# G3108.net
KiCad netlist of a schematic drawn in EasyEDA Pro
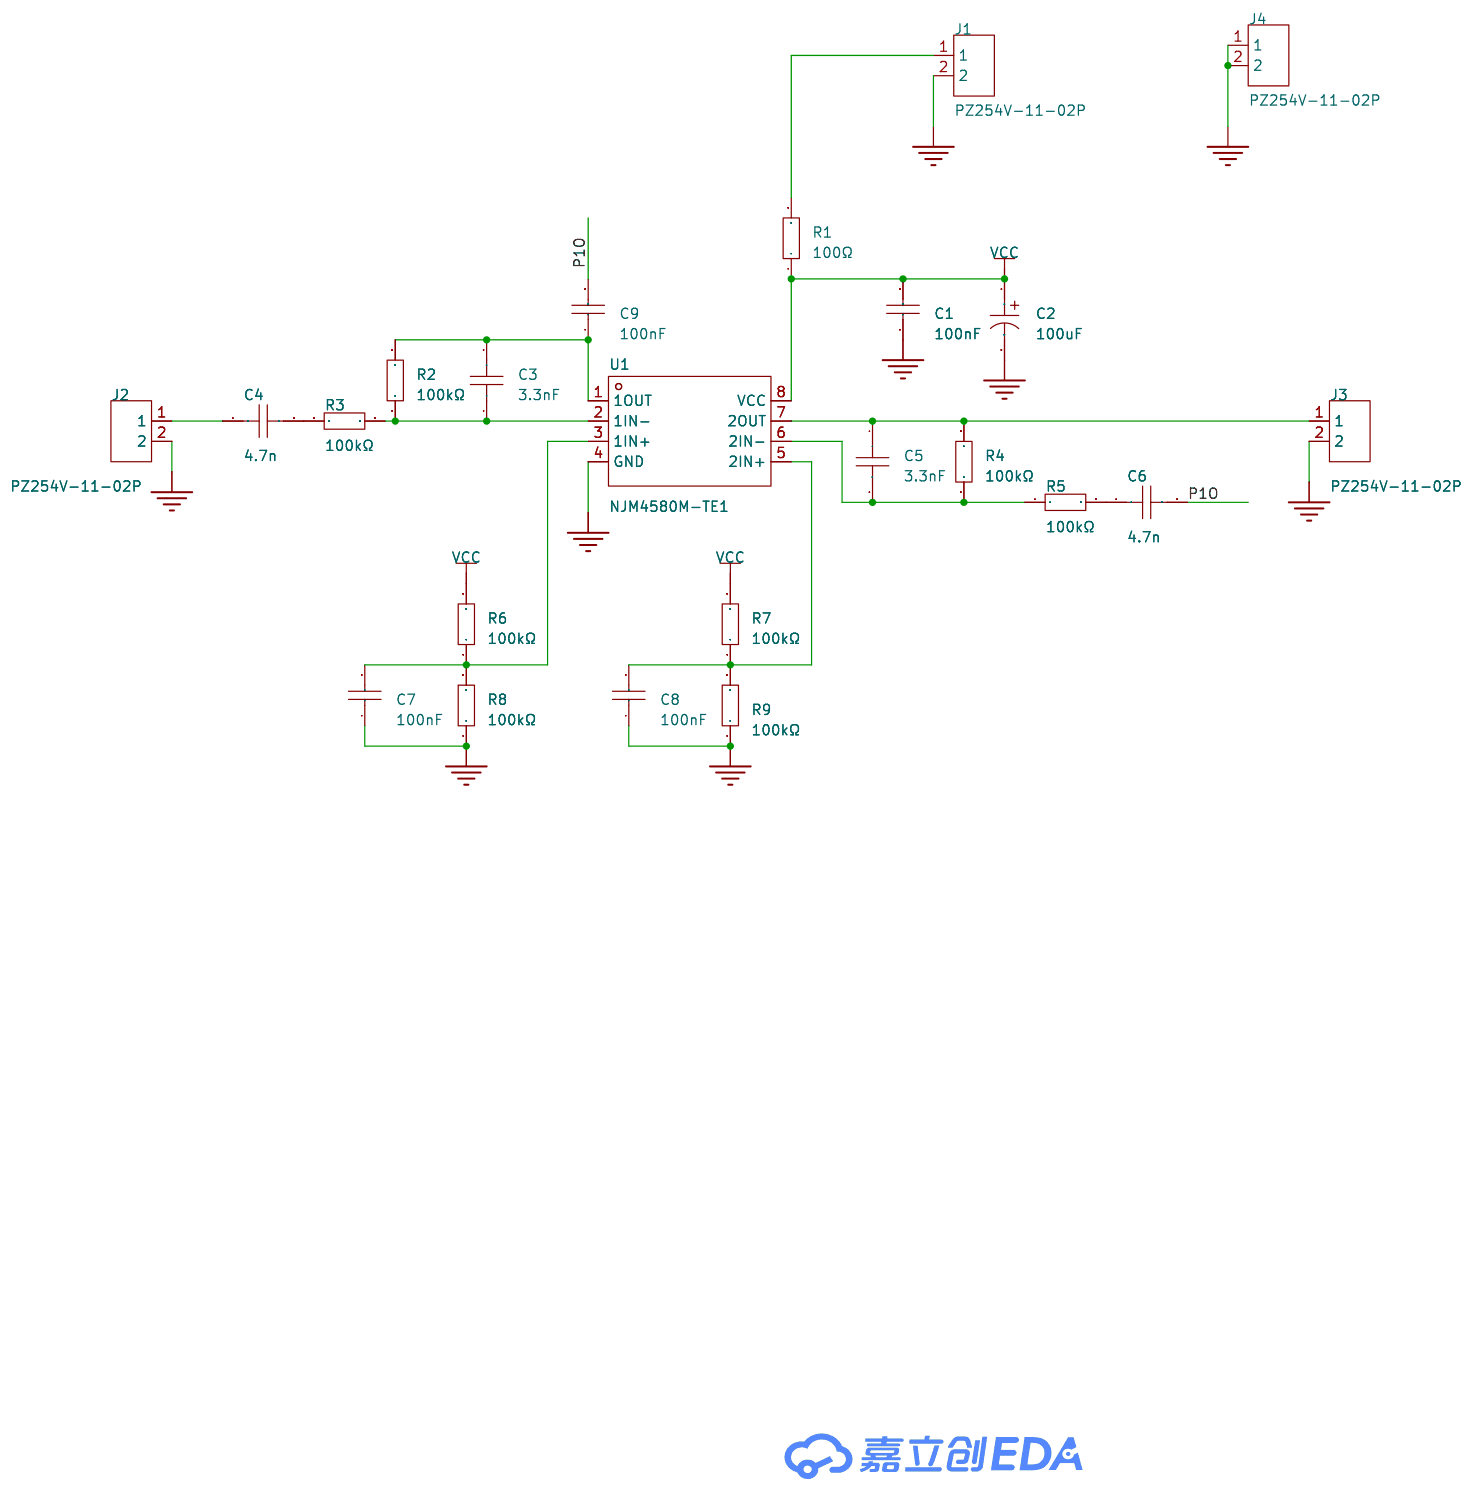
[diagram p0: schematic sheet]

(export (version "E")
  (design (tool "Eeschema 10.0.6"))
  (components
    (comp (ref "C1")
      (value "100nF")
      (footprint "easyedapro:C0603")
      (description "容值:100nF;精度:±5%;额定电压:50V;材质(温度系数):X7R;")
      (fields
        (field (name "Manufacturer Part") "CC0603JRX7R9BB104")
        (field (name "Manufacturer") "YAGEO(国巨)")
      )
      (libsource (lib "easyedapro") (part "CC0603JRX7R9BB104"))
    )
    (comp (ref "C2")
      (value "100uF")
      (footprint "easyedapro:CAP-SMD_L3.2-W1.6")
      (description "容值:100uF;精度:±20%;额定电压:7V;等效串联电阻(ESR):70mΩ@100kHz;")
      (fields
        (field (name "Manufacturer Part") "T55A107M007C0070")
        (field (name "Manufacturer") "VISHAY(威世)")
      )
      (libsource (lib "easyedapro") (part "T55A107M007C0070"))
    )
    (comp (ref "C3")
      (value "3.3nF")
      (footprint "easyedapro:C0603")
      (description "容值:3.3nF;精度:±1%;额定电压:50V;温度系数:NP0;")
      (fields
        (field (name "Manufacturer Part") "CC0603FRNPO9BN332")
        (field (name "Manufacturer") "YAGEO(国巨)")
      )
      (libsource (lib "easyedapro") (part "CC0603FRNPO9BN332"))
    )
    (comp (ref "C4")
      (value "4.7n")
      (footprint "easyedapro:C0603")
      (description "容值:3.3nF;精度:±1%;额定电压:50V;温度系数:NP0;")
      (fields
        (field (name "Manufacturer Part") "CC0603FRNPO9BN332")
        (field (name "Manufacturer") "YAGEO(国巨)")
      )
      (libsource (lib "easyedapro") (part "CC0603FRNPO9BN332"))
    )
    (comp (ref "C5")
      (value "3.3nF")
      (footprint "easyedapro:C0603")
      (description "容值:3.3nF;精度:±1%;额定电压:50V;温度系数:NP0;")
      (fields
        (field (name "Manufacturer Part") "CC0603FRNPO9BN332")
        (field (name "Manufacturer") "YAGEO(国巨)")
      )
      (libsource (lib "easyedapro") (part "CC0603FRNPO9BN332"))
    )
    (comp (ref "C6")
      (value "4.7n")
      (footprint "easyedapro:C0603")
      (description "容值:3.3nF;精度:±1%;额定电压:50V;温度系数:NP0;")
      (fields
        (field (name "Manufacturer Part") "CC0603FRNPO9BN332")
        (field (name "Manufacturer") "YAGEO(国巨)")
      )
      (libsource (lib "easyedapro") (part "CC0603FRNPO9BN332"))
    )
    (comp (ref "C7")
      (value "100nF")
      (footprint "easyedapro:C0603")
      (description "容值:100nF;精度:±5%;额定电压:50V;材质(温度系数):X7R;")
      (fields
        (field (name "Manufacturer Part") "CC0603JRX7R9BB104")
        (field (name "Manufacturer") "YAGEO(国巨)")
      )
      (libsource (lib "easyedapro") (part "CC0603JRX7R9BB104"))
    )
    (comp (ref "C8")
      (value "100nF")
      (footprint "easyedapro:C0603")
      (description "容值:100nF;精度:±5%;额定电压:50V;材质(温度系数):X7R;")
      (fields
        (field (name "Manufacturer Part") "CC0603JRX7R9BB104")
        (field (name "Manufacturer") "YAGEO(国巨)")
      )
      (libsource (lib "easyedapro") (part "CC0603JRX7R9BB104"))
    )
    (comp (ref "C9")
      (value "100nF")
      (footprint "easyedapro:C0603")
      (description "容值:100nF;精度:±5%;额定电压:50V;材质(温度系数):X7R;")
      (fields
        (field (name "Manufacturer Part") "CC0603JRX7R9BB104")
        (field (name "Manufacturer") "YAGEO(国巨)")
      )
      (libsource (lib "easyedapro") (part "CC0603JRX7R9BB104"))
    )
    (comp (ref "J1")
      (value "PZ254V-11-02P")
      (footprint "easyedapro:HDR-TH_2P-P2.54-V-M")
      (fields (field (name "Manufacturer") "XFCN(兴飞)"))
      (libsource (lib "easyedapro") (part "PZ254V-11-02P"))
    )
    (comp (ref "J2")
      (value "PZ254V-11-02P")
      (footprint "easyedapro:HDR-TH_2P-P2.54-V-M")
      (fields (field (name "Manufacturer") "XFCN(兴飞)"))
      (libsource (lib "easyedapro") (part "PZ254V-11-02P"))
    )
    (comp (ref "J3")
      (value "PZ254V-11-02P")
      (footprint "easyedapro:HDR-TH_2P-P2.54-V-M")
      (fields (field (name "Manufacturer") "XFCN(兴飞)"))
      (libsource (lib "easyedapro") (part "PZ254V-11-02P"))
    )
    (comp (ref "J4")
      (value "PZ254V-11-02P")
      (footprint "easyedapro:HDR-TH_2P-P2.54-V-M")
      (fields (field (name "Manufacturer") "XFCN(兴飞)"))
      (libsource (lib "easyedapro") (part "PZ254V-11-02P"))
    )
    (comp (ref "R1")
      (value "100Ω")
      (footprint "easyedapro:R0603")
      (description "电阻类型:厚膜电阻;阻值:100Ω;精度:±1%;功率:100mW;最大工作电压:75V;温度系数:±100ppm/°C;")
      (fields (field (name "Manufacturer Part") "RC0603FR-07100RL") (field (name "Manufacturer") "YAGEO(国巨)"))
      (libsource (lib "easyedapro") (part "RC0603FR-07100RL"))
    )
    (comp (ref "R2")
      (value "100kΩ")
      (footprint "easyedapro:R0603")
      (description "电阻类型:厚膜电阻;阻值:100kΩ;精度:±1%;功率:100mW;最大工作电压:75V;温度系数:±100ppm/°C;")
      (fields (field (name "Manufacturer Part") "RC0603FR-07100KL") (field (name "Manufacturer") "YAGEO(国巨)"))
      (libsource (lib "easyedapro") (part "RC0603FR-07100KL"))
    )
    (comp (ref "R3")
      (value "100kΩ")
      (footprint "easyedapro:R0603")
      (description "电阻类型:厚膜电阻;阻值:100kΩ;精度:±1%;功率:100mW;最大工作电压:75V;温度系数:±100ppm/°C;")
      (fields (field (name "Manufacturer Part") "RC0603FR-07100KL") (field (name "Manufacturer") "YAGEO(国巨)"))
      (libsource (lib "easyedapro") (part "RC0603FR-07100KL"))
    )
    (comp (ref "R4")
      (value "100kΩ")
      (footprint "easyedapro:R0603")
      (description "电阻类型:厚膜电阻;阻值:100kΩ;精度:±1%;功率:100mW;最大工作电压:75V;温度系数:±100ppm/°C;")
      (fields (field (name "Manufacturer Part") "RC0603FR-07100KL") (field (name "Manufacturer") "YAGEO(国巨)"))
      (libsource (lib "easyedapro") (part "RC0603FR-07100KL"))
    )
    (comp (ref "R5")
      (value "100kΩ")
      (footprint "easyedapro:R0603")
      (description "电阻类型:厚膜电阻;阻值:100kΩ;精度:±1%;功率:100mW;最大工作电压:75V;温度系数:±100ppm/°C;")
      (fields (field (name "Manufacturer Part") "RC0603FR-07100KL") (field (name "Manufacturer") "YAGEO(国巨)"))
      (libsource (lib "easyedapro") (part "RC0603FR-07100KL"))
    )
    (comp (ref "R6")
      (value "100kΩ")
      (footprint "easyedapro:R0603")
      (description "电阻类型:厚膜电阻;阻值:100kΩ;精度:±1%;功率:100mW;最大工作电压:75V;温度系数:±100ppm/°C;")
      (fields (field (name "Manufacturer Part") "RC0603FR-07100KL") (field (name "Manufacturer") "YAGEO(国巨)"))
      (libsource (lib "easyedapro") (part "RC0603FR-07100KL"))
    )
    (comp (ref "R7")
      (value "100kΩ")
      (footprint "easyedapro:R0603")
      (description "电阻类型:厚膜电阻;阻值:100kΩ;精度:±1%;功率:100mW;最大工作电压:75V;温度系数:±100ppm/°C;")
      (fields (field (name "Manufacturer Part") "RC0603FR-07100KL") (field (name "Manufacturer") "YAGEO(国巨)"))
      (libsource (lib "easyedapro") (part "RC0603FR-07100KL"))
    )
    (comp (ref "R8")
      (value "100kΩ")
      (footprint "easyedapro:R0603")
      (description "电阻类型:厚膜电阻;阻值:100kΩ;精度:±1%;功率:100mW;最大工作电压:75V;温度系数:±100ppm/°C;")
      (fields (field (name "Manufacturer Part") "RC0603FR-07100KL") (field (name "Manufacturer") "YAGEO(国巨)"))
      (libsource (lib "easyedapro") (part "RC0603FR-07100KL"))
    )
    (comp (ref "R9")
      (value "100kΩ")
      (footprint "easyedapro:R0603")
      (description "电阻类型:厚膜电阻;阻值:100kΩ;精度:±1%;功率:100mW;最大工作电压:75V;温度系数:±100ppm/°C;")
      (fields (field (name "Manufacturer Part") "RC0603FR-07100KL") (field (name "Manufacturer") "YAGEO(国巨)"))
      (libsource (lib "easyedapro") (part "RC0603FR-07100KL"))
    )
    (comp (ref "U1")
      (value "NJM4580M-TE1")
      (footprint "easyedapro:SO-8_L5.2-W4.4-P1.27-LS7.0-BL")
      (description "放大器数:双路;轨到轨:-;增益带宽积(GBP):15MHz;输入失调电压(Vos):3mV;压摆率(SR):5V/us;输入偏置电流(Ib):200nA;")
      (fields (field (name "Manufacturer") "JRC"))
      (libsource (lib "easyedapro") (part "NJM4580M-TE1"))
    )
  )
  (nets
    (net (code "1") (name "/P1O") (class "Default")
      (node (ref "C6") (pin "2") (pinfunction "2_2") (pintype "unspecified"))
      (node (ref "C9") (pin "2") (pinfunction "2_2") (pintype "input"))
    )
    (net (code "2") (name "GND") (class "Default")
      (node (ref "C1") (pin "1") (pinfunction "1_1") (pintype "input"))
      (node (ref "C2") (pin "2") (pinfunction "2_2") (pintype "input"))
      (node (ref "C7") (pin "1") (pinfunction "1_1") (pintype "input"))
      (node (ref "C8") (pin "1") (pinfunction "1_1") (pintype "input"))
      (node (ref "J1") (pin "2") (pinfunction "2_2") (pintype "unspecified"))
      (node (ref "J2") (pin "2") (pinfunction "2_2") (pintype "unspecified"))
      (node (ref "J3") (pin "2") (pinfunction "2_2") (pintype "unspecified"))
      (node (ref "J4") (pin "1") (pinfunction "1_1") (pintype "unspecified"))
      (node (ref "J4") (pin "2") (pinfunction "2_2") (pintype "unspecified"))
      (node (ref "R8") (pin "1") (pinfunction "1_1") (pintype "unspecified"))
      (node (ref "R9") (pin "1") (pinfunction "1_1") (pintype "unspecified"))
      (node (ref "U1") (pin "4") (pinfunction "GND_4") (pintype "unspecified"))
    )
    (net (code "3") (name "Net-(C4-Pad1)") (class "Default")
      (node (ref "C4") (pin "1") (pinfunction "1_1") (pintype "unspecified"))
      (node (ref "J2") (pin "1") (pinfunction "1_1") (pintype "unspecified"))
    )
    (net (code "4") (name "Net-(C4-Pad2)") (class "Default")
      (node (ref "C4") (pin "2") (pinfunction "2_2") (pintype "unspecified"))
      (node (ref "R3") (pin "1") (pinfunction "1_1") (pintype "unspecified"))
    )
    (net (code "5") (name "Net-(C6-Pad1)") (class "Default")
      (node (ref "C6") (pin "1") (pinfunction "1_1") (pintype "unspecified"))
      (node (ref "R5") (pin "2") (pinfunction "2_2") (pintype "unspecified"))
    )
    (net (code "6") (name "Net-(J1-Pad1)") (class "Default")
      (node (ref "J1") (pin "1") (pinfunction "1_1") (pintype "unspecified"))
      (node (ref "R1") (pin "2") (pinfunction "2_2") (pintype "input"))
    )
    (net (code "7") (name "Net-(U1-1IN+)") (class "Default")
      (node (ref "C7") (pin "2") (pinfunction "2_2") (pintype "input"))
      (node (ref "R6") (pin "1") (pinfunction "1_1") (pintype "unspecified"))
      (node (ref "R8") (pin "2") (pinfunction "2_2") (pintype "unspecified"))
      (node (ref "U1") (pin "3") (pinfunction "1IN+_3") (pintype "unspecified"))
    )
    (net (code "8") (name "Net-(U1-1IN-)") (class "Default")
      (node (ref "C3") (pin "1") (pinfunction "1_1") (pintype "unspecified"))
      (node (ref "R2") (pin "1") (pinfunction "1_1") (pintype "unspecified"))
      (node (ref "R3") (pin "2") (pinfunction "2_2") (pintype "unspecified"))
      (node (ref "U1") (pin "2") (pinfunction "1IN-_2") (pintype "unspecified"))
    )
    (net (code "9") (name "Net-(U1-1OUT)") (class "Default")
      (node (ref "C3") (pin "2") (pinfunction "2_2") (pintype "unspecified"))
      (node (ref "C9") (pin "1") (pinfunction "1_1") (pintype "input"))
      (node (ref "R2") (pin "2") (pinfunction "2_2") (pintype "unspecified"))
      (node (ref "U1") (pin "1") (pinfunction "1OUT_1") (pintype "unspecified"))
    )
    (net (code "10") (name "Net-(U1-2IN+)") (class "Default")
      (node (ref "C8") (pin "2") (pinfunction "2_2") (pintype "input"))
      (node (ref "R7") (pin "1") (pinfunction "1_1") (pintype "unspecified"))
      (node (ref "R9") (pin "2") (pinfunction "2_2") (pintype "unspecified"))
      (node (ref "U1") (pin "5") (pinfunction "2IN+_5") (pintype "unspecified"))
    )
    (net (code "11") (name "Net-(U1-2IN-)") (class "Default")
      (node (ref "C5") (pin "2") (pinfunction "2_2") (pintype "unspecified"))
      (node (ref "R4") (pin "1") (pinfunction "1_1") (pintype "unspecified"))
      (node (ref "R5") (pin "1") (pinfunction "1_1") (pintype "unspecified"))
      (node (ref "U1") (pin "6") (pinfunction "2IN-_6") (pintype "unspecified"))
    )
    (net (code "12") (name "Net-(U1-2OUT)") (class "Default")
      (node (ref "C5") (pin "1") (pinfunction "1_1") (pintype "unspecified"))
      (node (ref "J3") (pin "1") (pinfunction "1_1") (pintype "unspecified"))
      (node (ref "R4") (pin "2") (pinfunction "2_2") (pintype "unspecified"))
      (node (ref "U1") (pin "7") (pinfunction "2OUT_7") (pintype "unspecified"))
    )
    (net (code "13") (name "VCC") (class "Default")
      (node (ref "C1") (pin "2") (pinfunction "2_2") (pintype "input"))
      (node (ref "C2") (pin "1") (pinfunction "1_1") (pintype "input"))
      (node (ref "R1") (pin "1") (pinfunction "1_1") (pintype "input"))
      (node (ref "R6") (pin "2") (pinfunction "2_2") (pintype "unspecified"))
      (node (ref "R7") (pin "2") (pinfunction "2_2") (pintype "unspecified"))
      (node (ref "U1") (pin "8") (pinfunction "VCC_8") (pintype "unspecified"))
    )
  )
)
